# drin.net
KiCad netlist of a schematic drawn in Altium Designer
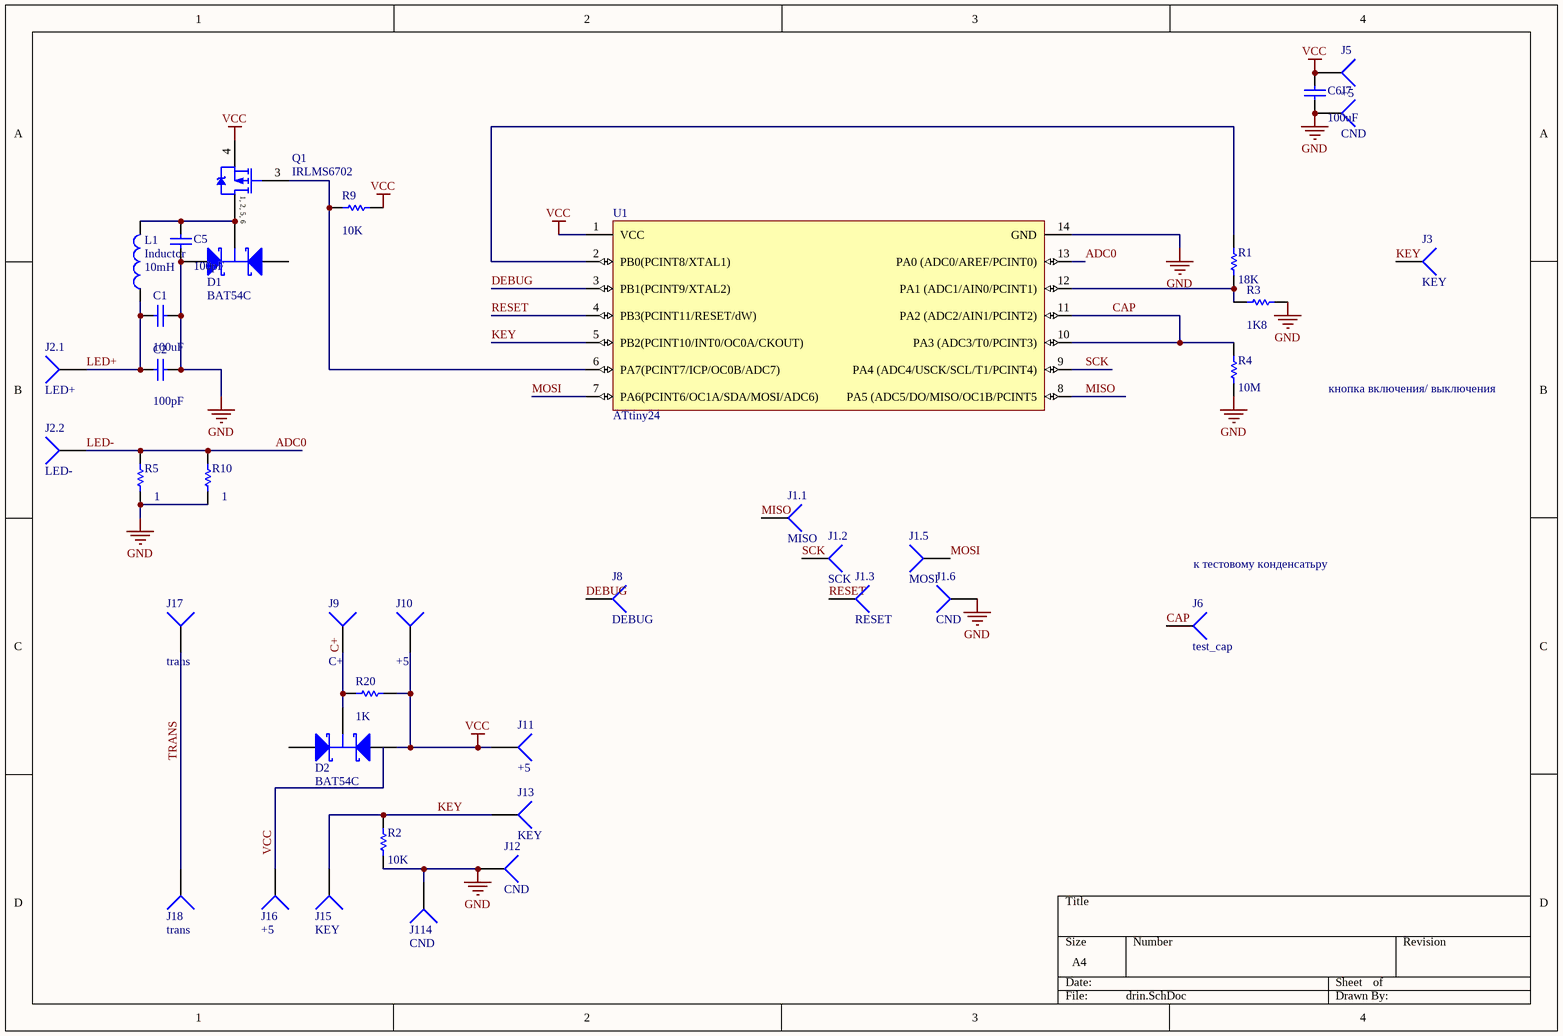
[diagram p0: drin.SchDoc]

(export (version "E")
  (design (tool "Eeschema 10.0.6"))
  (components
    (comp (ref "C1")
      (value "100uF")
      (footprint "C1210")
      (description "Capacitor (Semiconductor SIM Model)")
      (fields (field (name "PUBLISHER") "Altium Limited"))
      (libsource (lib "Miscellaneous Devices") (part "Cap Semi"))
    )
    (comp (ref "C2")
      (value "100pF")
      (footprint "2012[0805]A")
      (description "Capacitor (Semiconductor SIM Model)")
      (fields (field (name "PUBLISHER") "Altium Limited"))
      (libsource (lib "Miscellaneous Devices") (part "Cap Semi"))
    )
    (comp (ref "C5")
      (value "100pF")
      (footprint "1608[0603]A")
      (description "Capacitor (Semiconductor SIM Model)")
      (fields (field (name "PUBLISHER") "Altium Limited"))
      (libsource (lib "Miscellaneous Devices") (part "Cap Semi"))
    )
    (comp (ref "C6")
      (value "100uF")
      (footprint "C1210")
      (description "Capacitor (Semiconductor SIM Model)")
      (fields (field (name "PUBLISHER") "Altium Limited"))
      (libsource (lib "Miscellaneous Devices") (part "Cap Semi"))
    )
    (comp (ref "D1")
      (value "BAT54C")
      (footprint "SOT23_N")
      (description "Schottky Barrier Double Diode")
      (fields (field (name "PUBLISHER") "Altium Limited"))
      (libsource (lib "Philips Discrete Diode - Schottky") (part "BAT54C"))
    )
    (comp (ref "D2")
      (value "BAT54C")
      (footprint "SOT23_N")
      (description "Schottky Barrier Double Diode")
      (fields (field (name "PUBLISHER") "Altium Limited"))
      (libsource (lib "Philips Discrete Diode - Schottky") (part "BAT54C"))
    )
    (comp (ref "J1.1")
      (value "MISO")
      (footprint "PIN1")
      (description "Socket")
      (fields (field (name "PUBLISHER") "Altium Limited"))
      (libsource (lib "Miscellaneous Connectors") (part "Socket"))
    )
    (comp (ref "J1.2")
      (value "SCK")
      (footprint "PIN1")
      (description "Socket")
      (fields (field (name "PUBLISHER") "Altium Limited"))
      (libsource (lib "Miscellaneous Connectors") (part "Socket"))
    )
    (comp (ref "J1.3")
      (value "RESET")
      (footprint "PIN1")
      (description "Socket")
      (fields (field (name "PUBLISHER") "Altium Limited"))
      (libsource (lib "Miscellaneous Connectors") (part "Socket"))
    )
    (comp (ref "J1.5")
      (value "MOSI")
      (footprint "PIN1")
      (description "Socket")
      (fields (field (name "PUBLISHER") "Altium Limited"))
      (libsource (lib "Miscellaneous Connectors") (part "Socket"))
    )
    (comp (ref "J1.6")
      (value "CND")
      (footprint "PIN1")
      (description "Socket")
      (fields (field (name "PUBLISHER") "Altium Limited"))
      (libsource (lib "Miscellaneous Connectors") (part "Socket"))
    )
    (comp (ref "J2.1")
      (value "LED+")
      (footprint "PIN1")
      (description "Socket")
      (fields (field (name "PUBLISHER") "Altium Limited"))
      (libsource (lib "Miscellaneous Connectors") (part "Socket"))
    )
    (comp (ref "J2.2")
      (value "LED-")
      (footprint "PIN1")
      (description "Socket")
      (fields (field (name "PUBLISHER") "Altium Limited"))
      (libsource (lib "Miscellaneous Connectors") (part "Socket"))
    )
    (comp (ref "J3")
      (value "KEY")
      (footprint "PIN1")
      (description "Socket")
      (fields (field (name "PUBLISHER") "Altium Limited"))
      (libsource (lib "Miscellaneous Connectors") (part "Socket"))
    )
    (comp (ref "J5")
      (value "+5")
      (footprint "PIN1")
      (description "Socket")
      (fields (field (name "PUBLISHER") "Altium Limited"))
      (libsource (lib "Miscellaneous Connectors") (part "Socket"))
    )
    (comp (ref "J6")
      (value "test_cap")
      (footprint "PIN1")
      (description "Socket")
      (fields (field (name "PUBLISHER") "Altium Limited"))
      (libsource (lib "Miscellaneous Connectors") (part "Socket"))
    )
    (comp (ref "J7")
      (value "CND")
      (footprint "PIN1")
      (description "Socket")
      (fields (field (name "PUBLISHER") "Altium Limited"))
      (libsource (lib "Miscellaneous Connectors") (part "Socket"))
    )
    (comp (ref "J8")
      (value "DEBUG")
      (footprint "PIN1")
      (description "Socket")
      (fields (field (name "PUBLISHER") "Altium Limited"))
      (libsource (lib "Miscellaneous Connectors") (part "Socket"))
    )
    (comp (ref "J9")
      (value "C+")
      (footprint "PIN1")
      (description "Socket")
      (fields (field (name "PUBLISHER") "Altium Limited"))
      (libsource (lib "Miscellaneous Connectors") (part "Socket"))
    )
    (comp (ref "J10")
      (value "+5")
      (footprint "PIN1")
      (description "Socket")
      (fields (field (name "PUBLISHER") "Altium Limited"))
      (libsource (lib "Miscellaneous Connectors") (part "Socket"))
    )
    (comp (ref "J11")
      (value "+5")
      (footprint "PIN1")
      (description "Socket")
      (fields (field (name "PUBLISHER") "Altium Limited"))
      (libsource (lib "Miscellaneous Connectors") (part "Socket"))
    )
    (comp (ref "J12")
      (value "CND")
      (footprint "PIN1")
      (description "Socket")
      (fields (field (name "PUBLISHER") "Altium Limited"))
      (libsource (lib "Miscellaneous Connectors") (part "Socket"))
    )
    (comp (ref "J13")
      (value "KEY")
      (footprint "PIN1")
      (description "Socket")
      (fields (field (name "PUBLISHER") "Altium Limited"))
      (libsource (lib "Miscellaneous Connectors") (part "Socket"))
    )
    (comp (ref "J15")
      (value "KEY")
      (footprint "PIN1")
      (description "Socket")
      (fields (field (name "PUBLISHER") "Altium Limited"))
      (libsource (lib "Miscellaneous Connectors") (part "Socket"))
    )
    (comp (ref "J16")
      (value "+5")
      (footprint "PIN1")
      (description "Socket")
      (fields (field (name "PUBLISHER") "Altium Limited"))
      (libsource (lib "Miscellaneous Connectors") (part "Socket"))
    )
    (comp (ref "J17")
      (value "trans")
      (footprint "PIN1")
      (description "Socket")
      (fields (field (name "PUBLISHER") "Altium Limited"))
      (libsource (lib "Miscellaneous Connectors") (part "Socket"))
    )
    (comp (ref "J18")
      (value "trans")
      (footprint "PIN1")
      (description "Socket")
      (fields (field (name "PUBLISHER") "Altium Limited"))
      (libsource (lib "Miscellaneous Connectors") (part "Socket"))
    )
    (comp (ref "J114")
      (value "CND")
      (footprint "PIN1")
      (description "Socket")
      (fields (field (name "PUBLISHER") "Altium Limited"))
      (libsource (lib "Miscellaneous Connectors") (part "Socket"))
    )
    (comp (ref "L1")
      (value "Inductor")
      (footprint "6332[2512]")
      (fields (field (name "ALTIUM_VALUE") "10mH") (field (name "PUBLISHER") "Altium Limited"))
      (libsource (lib "Miscellaneous Devices") (part "Inductor"))
    )
    (comp (ref "Q1")
      (value "IRLMS6702")
      (footprint "Micro6")
      (description "HEXFET Power MOSFET")
      (fields (field (name "PUBLISHER") "Altium Limited"))
      (libsource (lib "IR Discrete MOSFET - Power") (part "IRLMS6702"))
    )
    (comp (ref "R1")
      (value "18K")
      (footprint "1608[0603]A")
      (description "Semiconductor Resistor")
      (fields (field (name "PUBLISHER") "Altium Limited"))
      (libsource (lib "Miscellaneous Devices") (part "Res Semi"))
    )
    (comp (ref "R2")
      (value "10K")
      (footprint "1608[0603]A")
      (description "Semiconductor Resistor")
      (fields (field (name "PUBLISHER") "Altium Limited"))
      (libsource (lib "Miscellaneous Devices") (part "Res Semi"))
    )
    (comp (ref "R3")
      (value "1K8")
      (footprint "1608[0603]A")
      (description "Semiconductor Resistor")
      (fields (field (name "PUBLISHER") "Altium Limited"))
      (libsource (lib "Miscellaneous Devices") (part "Res Semi"))
    )
    (comp (ref "R4")
      (value "10M")
      (footprint "1608[0603]A")
      (description "Semiconductor Resistor")
      (fields (field (name "PUBLISHER") "Altium Limited"))
      (libsource (lib "Miscellaneous Devices") (part "Res Semi"))
    )
    (comp (ref "R5")
      (value "1")
      (footprint "1608[0603]A")
      (description "Semiconductor Resistor")
      (fields (field (name "PUBLISHER") "Altium Limited"))
      (libsource (lib "Miscellaneous Devices") (part "Res Semi"))
    )
    (comp (ref "R9")
      (value "10K")
      (footprint "1608[0603]A")
      (description "Semiconductor Resistor")
      (fields (field (name "PUBLISHER") "Altium Limited"))
      (libsource (lib "Miscellaneous Devices") (part "Res Semi"))
    )
    (comp (ref "R10")
      (value "1")
      (footprint "1608[0603]A")
      (description "Semiconductor Resistor")
      (fields (field (name "PUBLISHER") "Altium Limited"))
      (libsource (lib "Miscellaneous Devices") (part "Res Semi"))
    )
    (comp (ref "R20")
      (value "1K")
      (footprint "1608[0603]A")
      (description "Semiconductor Resistor")
      (fields (field (name "PUBLISHER") "Altium Limited"))
      (libsource (lib "Miscellaneous Devices") (part "Res Semi"))
    )
    (comp (ref "U1")
      (value "ATtiny24")
      (footprint "SOIC14_M")
      (description "8-Bit AVR Microcontroller with 1K Byte of Flash Memory")
      (fields (field (name "PUBLISHER") "Altium Limited"))
      (libsource (lib "Integrated_Library1") (part "ATtiny24"))
    )
  )
  (nets
    (net (code "1") (name "/ADC0") (class "Default")
      (node (ref "J2.2") (pin "1") (pinfunction "1_1") (pintype "passive"))
      (node (ref "R10") (pin "2") (pinfunction "2_2") (pintype "passive"))
      (node (ref "R5") (pin "2") (pinfunction "2_2") (pintype "passive"))
      (node (ref "U1") (pin "13") (pinfunction "PA0_(ADC0/AREF/PCINT0)_13") (pintype "bidirectional"))
    )
    (net (code "2") (name "/C+") (class "Default")
      (node (ref "D2") (pin "3") (pinfunction "K_3") (pintype "passive"))
      (node (ref "J9") (pin "1") (pinfunction "1_1") (pintype "passive"))
      (node (ref "R20") (pin "1") (pinfunction "1_1") (pintype "passive"))
    )
    (net (code "3") (name "/CAP") (class "Default")
      (node (ref "J6") (pin "1") (pinfunction "1_1") (pintype "passive"))
      (node (ref "R4") (pin "2") (pinfunction "2_2") (pintype "passive"))
      (node (ref "U1") (pin "10") (pinfunction "PA3_(ADC3/T0/PCINT3)_10") (pintype "bidirectional"))
      (node (ref "U1") (pin "11") (pinfunction "PA2_(ADC2/AIN1/PCINT2)_11") (pintype "bidirectional"))
    )
    (net (code "4") (name "/DEBUG") (class "Default")
      (node (ref "J8") (pin "1") (pinfunction "1_1") (pintype "passive"))
      (node (ref "U1") (pin "3") (pinfunction "PB1(PCINT9/XTAL2)_3") (pintype "bidirectional"))
    )
    (net (code "5") (name "/KEY") (class "Default")
      (node (ref "J13") (pin "1") (pinfunction "1_1") (pintype "passive"))
      (node (ref "J15") (pin "1") (pinfunction "1_1") (pintype "passive"))
      (node (ref "J3") (pin "1") (pinfunction "1_1") (pintype "passive"))
      (node (ref "R2") (pin "2") (pinfunction "2_2") (pintype "passive"))
      (node (ref "U1") (pin "5") (pinfunction "PB2(PCINT10/INT0/OC0A/CKOUT)_5") (pintype "bidirectional"))
    )
    (net (code "6") (name "/LED+") (class "Default")
      (node (ref "C1") (pin "1") (pinfunction "1_1") (pintype "passive"))
      (node (ref "C2") (pin "1") (pinfunction "1_1") (pintype "passive"))
      (node (ref "J2.1") (pin "1") (pinfunction "1_1") (pintype "passive"))
      (node (ref "L1") (pin "1") (pinfunction "1_1") (pintype "passive"))
    )
    (net (code "7") (name "/MISO") (class "Default")
      (node (ref "J1.1") (pin "1") (pinfunction "1_1") (pintype "passive"))
      (node (ref "U1") (pin "8") (pinfunction "PA5_(ADC5/DO/MISO/OC1B/PCINT5_8") (pintype "bidirectional"))
    )
    (net (code "8") (name "/MOSI") (class "Default")
      (node (ref "J1.5") (pin "1") (pinfunction "1_1") (pintype "passive"))
      (node (ref "U1") (pin "7") (pinfunction "PA6(PCINT6/OC1A/SDA/MOSI/ADC6)_7") (pintype "bidirectional"))
    )
    (net (code "9") (name "/RESET") (class "Default")
      (node (ref "J1.3") (pin "1") (pinfunction "1_1") (pintype "passive"))
      (node (ref "U1") (pin "4") (pinfunction "PB3(PCINT11/RESET/dW)_4") (pintype "bidirectional"))
    )
    (net (code "10") (name "/SCK") (class "Default")
      (node (ref "J1.2") (pin "1") (pinfunction "1_1") (pintype "passive"))
      (node (ref "U1") (pin "9") (pinfunction "PA4_(ADC4/USCK/SCL/T1/PCINT4)_9") (pintype "bidirectional"))
    )
    (net (code "11") (name "/TRANS") (class "Default")
      (node (ref "J17") (pin "1") (pinfunction "1_1") (pintype "passive"))
      (node (ref "J18") (pin "1") (pinfunction "1_1") (pintype "passive"))
    )
    (net (code "12") (name "GND") (class "Default")
      (node (ref "C1") (pin "2") (pinfunction "2_2") (pintype "passive"))
      (node (ref "C2") (pin "2") (pinfunction "2_2") (pintype "passive"))
      (node (ref "C5") (pin "1") (pinfunction "1_1") (pintype "passive"))
      (node (ref "C6") (pin "1") (pinfunction "1_1") (pintype "passive"))
      (node (ref "D1") (pin "1") (pinfunction "A1_1") (pintype "passive"))
      (node (ref "J1.6") (pin "1") (pinfunction "1_1") (pintype "passive"))
      (node (ref "J114") (pin "1") (pinfunction "1_1") (pintype "passive"))
      (node (ref "J12") (pin "1") (pinfunction "1_1") (pintype "passive"))
      (node (ref "J7") (pin "1") (pinfunction "1_1") (pintype "passive"))
      (node (ref "R10") (pin "1") (pinfunction "1_1") (pintype "passive"))
      (node (ref "R2") (pin "1") (pinfunction "1_1") (pintype "passive"))
      (node (ref "R3") (pin "1") (pinfunction "1_1") (pintype "passive"))
      (node (ref "R4") (pin "1") (pinfunction "1_1") (pintype "passive"))
      (node (ref "R5") (pin "1") (pinfunction "1_1") (pintype "passive"))
      (node (ref "U1") (pin "14") (pinfunction "GND_14") (pintype "power_in"))
    )
    (net (code "13") (name "Net-(D1-K)") (class "Default")
      (node (ref "C5") (pin "2") (pinfunction "2_2") (pintype "passive"))
      (node (ref "D1") (pin "3") (pinfunction "K_3") (pintype "passive"))
      (node (ref "L1") (pin "2") (pinfunction "2_2") (pintype "passive"))
      (node (ref "Q1") (pin "1") (pinfunction "D_1") (pintype "passive"))
      (node (ref "Q1") (pin "2") (pinfunction "D_2") (pintype "passive"))
      (node (ref "Q1") (pin "5") (pinfunction "D_5") (pintype "passive"))
      (node (ref "Q1") (pin "6") (pinfunction "D_6") (pintype "passive"))
    )
    (net (code "14") (name "Net-(Q1-G)") (class "Default")
      (node (ref "Q1") (pin "3") (pinfunction "G_3") (pintype "passive"))
      (node (ref "R9") (pin "2") (pinfunction "2_2") (pintype "passive"))
      (node (ref "U1") (pin "6") (pinfunction "PA7(PCINT7/ICP/OC0B/ADC7)_6") (pintype "bidirectional"))
    )
    (net (code "15") (name "Net-(U1-PA1_(ADC1{slash}AIN0{slash}PCINT1))") (class "Default")
      (node (ref "R1") (pin "1") (pinfunction "1_1") (pintype "passive"))
      (node (ref "R3") (pin "2") (pinfunction "2_2") (pintype "passive"))
      (node (ref "U1") (pin "12") (pinfunction "PA1_(ADC1/AIN0/PCINT1)_12") (pintype "bidirectional"))
    )
    (net (code "16") (name "Net-(U1-PB0(PCINT8{slash}XTAL1))") (class "Default")
      (node (ref "R1") (pin "2") (pinfunction "2_2") (pintype "passive"))
      (node (ref "U1") (pin "2") (pinfunction "PB0(PCINT8/XTAL1)_2") (pintype "bidirectional"))
    )
    (net (code "17") (name "VCC") (class "Default")
      (node (ref "C6") (pin "2") (pinfunction "2_2") (pintype "passive"))
      (node (ref "D2") (pin "2") (pinfunction "A2_2") (pintype "passive"))
      (node (ref "J10") (pin "1") (pinfunction "1_1") (pintype "passive"))
      (node (ref "J11") (pin "1") (pinfunction "1_1") (pintype "passive"))
      (node (ref "J16") (pin "1") (pinfunction "1_1") (pintype "passive"))
      (node (ref "J5") (pin "1") (pinfunction "1_1") (pintype "passive"))
      (node (ref "Q1") (pin "4") (pinfunction "S_4") (pintype "passive"))
      (node (ref "R20") (pin "2") (pinfunction "2_2") (pintype "passive"))
      (node (ref "R9") (pin "1") (pinfunction "1_1") (pintype "passive"))
      (node (ref "U1") (pin "1") (pinfunction "VCC_1") (pintype "power_in"))
    )
    (net (code "18") (name "unconnected-(D1-A2-Pad2)") (class "Default")
      (node (ref "D1") (pin "2") (pinfunction "A2_2") (pintype "passive"))
    )
    (net (code "19") (name "unconnected-(D2-A1-Pad1)") (class "Default")
      (node (ref "D2") (pin "1") (pinfunction "A1_1") (pintype "passive"))
    )
  )
)
